# WireLessPhone_Power.net
KiCad netlist of a schematic drawn in Altium Designer
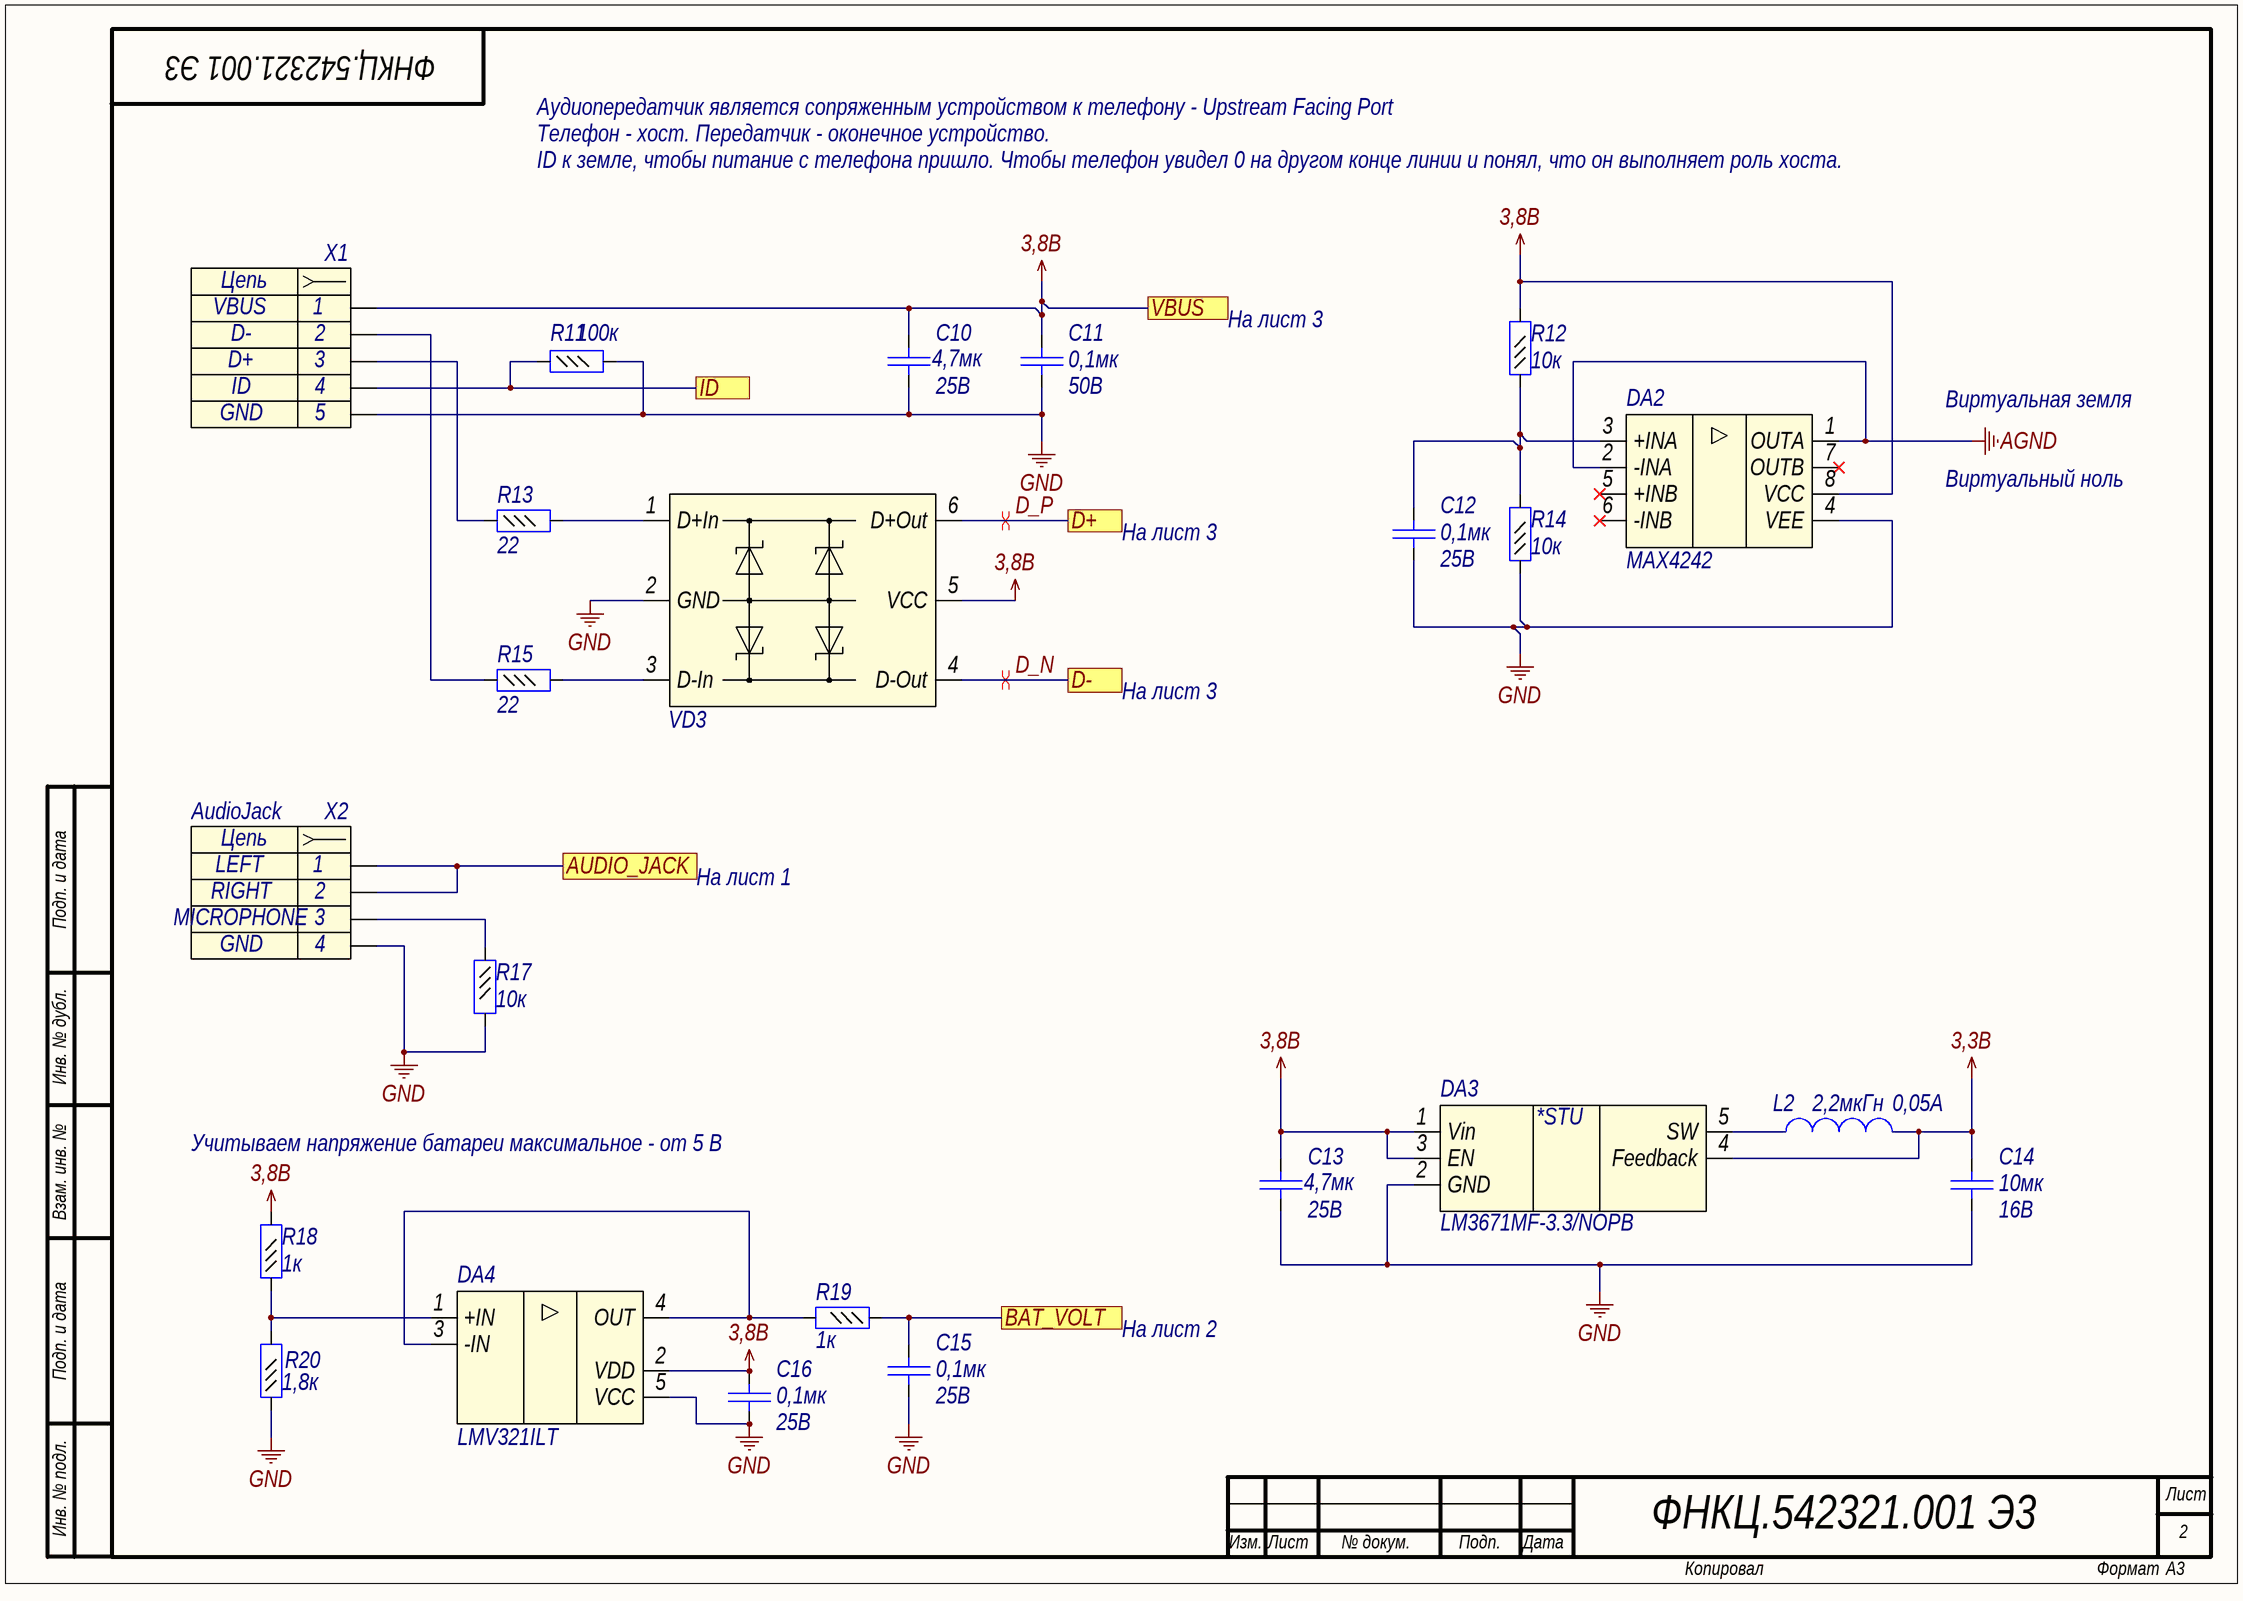
[diagram p0: WireLessPhone_Power.SchDoc]

(export (version "E")
  (design (tool "Eeschema 10.0.6"))
  (components
    (comp (ref "C10")
      (value "4,7мк")
      (footprint "C0805")
      (description "Конденсатор")
      (fields
        (field (name "VOLTAGE") "25B")
        (field (name "PART NUMBER") "GRM21BR61E475KA12L")
        (field (name "Comment") "Capacitor")
      )
      (libsource (lib "MOP44") (part "Capacitor"))
    )
    (comp (ref "C11")
      (value "0,1мк")
      (footprint "C0603")
      (description "Конденсатор")
      (fields
        (field (name "VOLTAGE") "50B")
        (field (name "PART NUMBER") "GRM188R71H104K")
        (field (name "Comment") "Capacitor")
      )
      (libsource (lib "MOP44") (part "Capacitor"))
    )
    (comp (ref "C12")
      (value "0,1мк")
      (footprint "C0402")
      (description "Конденсатор")
      (fields
        (field (name "VOLTAGE") "25B")
        (field (name "PART NUMBER") "GRM155F51E104Z**")
        (field (name "Comment") "Capacitor")
      )
      (libsource (lib "MOP44") (part "Capacitor"))
    )
    (comp (ref "C13")
      (value "4,7мк")
      (footprint "C0805")
      (description "Конденсатор")
      (fields
        (field (name "VOLTAGE") "25B")
        (field (name "PART NUMBER") "GRM21BR61E475KA12L")
        (field (name "Comment") "Capacitor")
      )
      (libsource (lib "MOP44") (part "Capacitor"))
    )
    (comp (ref "C14")
      (value "10мк")
      (footprint "C1206")
      (description "Конденсатор")
      (fields
        (field (name "VOLTAGE") "16В")
        (field (name "PART NUMBER") "GRM31CR71C106K*")
        (field (name "Comment") "Capacitor")
      )
      (libsource (lib "MOP44") (part "Capacitor"))
    )
    (comp (ref "C15")
      (value "0,1мк")
      (footprint "C0402")
      (description "Конденсатор")
      (fields
        (field (name "VOLTAGE") "25B")
        (field (name "PART NUMBER") "GRM155F51E104Z**")
        (field (name "Comment") "Capacitor")
      )
      (libsource (lib "MOP44") (part "Capacitor"))
    )
    (comp (ref "C16")
      (value "0,1мк")
      (footprint "C0402")
      (description "Конденсатор")
      (fields
        (field (name "VOLTAGE") "25B")
        (field (name "PART NUMBER") "GRM155F51E104Z**")
        (field (name "Comment") "Capacitor")
      )
      (libsource (lib "MOP44") (part "Capacitor"))
    )
    (comp (ref "DA2")
      (value "MAX4242")
      (footprint "8µMAX")
      (description "МИКРОМОЩНЫЙ Single/Dual/Quad, +1.8V/10µA, SOT23,  Beyond-the-Rails Op Amps")
      (fields (field (name "PART NUMBER") "MAX4242EUA"))
      (libsource (lib "MOP44") (part "MAX4242"))
    )
    (comp (ref "DA3")
      (value "LM3671MF-3.3/NOPB")
      (footprint "SOT23-5")
      (description "Step-Down DC-DC Converter")
      (fields (field (name "MANUFACTURER") "Texas Instruments"))
      (libsource (lib "MOP44") (part "LM3671MF-3.3/NOPB"))
    )
    (comp (ref "DA4")
      (value "LMV321ILT")
      (footprint "SOT23-5")
      (description "HIGH-DRIVE OPERATIONAL AMPLIFIERS WITH SHUTDOWN")
      (libsource (lib "MOP44") (part "LMV321ILT"))
    )
    (comp (ref "L2")
      (value "2,2мкГн")
      (footprint "L0805")
      (description "EMI Suppression Filter")
      (fields
        (field (name "RATED CURRENT") "0,05A")
        (field (name "PART NUMBER") "MLF2012A2R2KT000")
        (field (name "Comment") "Inductor")
      )
      (libsource (lib "MOP44") (part "Inductor"))
    )
    (comp (ref "R11")
      (value "100к")
      (footprint "R0402")
      (description "Резистор")
      (fields (field (name "PART NUMBER") "RC0402FR-07100KL") (field (name "POWER") "0,062Вт"))
      (libsource (lib "") (part "Resistor_0,062Вт_2"))
    )
    (comp (ref "R12")
      (value "10к")
      (footprint "R0402")
      (description "Резистор")
      (fields (field (name "PART NUMBER") "RC0402FR-0710KL") (field (name "POWER") "0,062Вт"))
      (libsource (lib "") (part "Resistor_0,062Вт_1"))
    )
    (comp (ref "R13")
      (value "22")
      (footprint "R0402")
      (description "Резистор")
      (fields (field (name "PART NUMBER") "RC0402FR-0722RL") (field (name "POWER") "0,062Вт"))
      (libsource (lib "") (part "Resistor_0,062Вт_2"))
    )
    (comp (ref "R14")
      (value "10к")
      (footprint "R0402")
      (description "Резистор")
      (fields (field (name "PART NUMBER") "RC0402FR-0710KL") (field (name "POWER") "0,062Вт"))
      (libsource (lib "") (part "Resistor_0,062Вт_1"))
    )
    (comp (ref "R15")
      (value "22")
      (footprint "R0402")
      (description "Резистор")
      (fields (field (name "PART NUMBER") "RC0402FR-0722RL") (field (name "POWER") "0,062Вт"))
      (libsource (lib "") (part "Resistor_0,062Вт_2"))
    )
    (comp (ref "R17")
      (value "10к")
      (footprint "R0402")
      (description "Резистор")
      (fields (field (name "PART NUMBER") "RC0402FR-0710KL") (field (name "POWER") "0,062Вт"))
      (libsource (lib "") (part "Resistor_0,062Вт_3"))
    )
    (comp (ref "R18")
      (value "1к")
      (footprint "R0402")
      (description "Резистор")
      (fields (field (name "PART NUMBER") "RC0402FR-071KL") (field (name "POWER") "0,062Вт"))
      (libsource (lib "") (part "Resistor_0,062Вт_1"))
    )
    (comp (ref "R19")
      (value "1к")
      (footprint "R0402")
      (description "Резистор")
      (fields (field (name "PART NUMBER") "RC0402FR-071KL") (field (name "POWER") "0,062Вт"))
      (libsource (lib "MOP44") (part "Resistor_0,062Вт"))
    )
    (comp (ref "R20")
      (value "1,8к")
      (footprint "R0402")
      (description "Резистор")
      (fields (field (name "PART NUMBER") "RC0402FR-071K8") (field (name "POWER") "0,062Вт"))
      (libsource (lib "") (part "Resistor_0,062Вт_1"))
    )
    (comp (ref "VD3")
      (value "USBUF")
      (footprint "SOT323-6L")
      (description "EMEMI filter and line termination for USB upstream ports")
      (fields (field (name "PART NUMBER") "USBUF02W6"))
      (libsource (lib "MOP44") (part "USBUF"))
    )
    (comp (ref "X1")
      (value "Header_5_sct")
      (footprint "5HOLE_SMALL")
      (description "Разъем - 5 конт. розетка")
      (libsource (lib "MOP44") (part "Header_5_sct"))
    )
    (comp (ref "X2")
      (value "AudioJack")
      (footprint "4HOLE_SMALL")
      (description "Разъем - 4 конт. розетка")
      (libsource (lib "MOP44") (part "Header_4_sct"))
    )
  )
  (nets
    (net (code "1") (name "/AUDIO_JACK") (class "Default")
      (node (ref "X2") (pin "1") (pinfunction "1_1") (pintype "passive"))
      (node (ref "X2") (pin "2") (pinfunction "2_2") (pintype "passive"))
    )
    (net (code "2") (name "/BAT_VOLT") (class "Default")
      (node (ref "C15") (pin "1") (pinfunction "1_1") (pintype "passive"))
      (node (ref "R19") (pin "1") (pinfunction "1_1") (pintype "passive"))
    )
    (net (code "3") (name "/D_N") (class "Default")
      (node (ref "VD3") (pin "4") (pinfunction "D-Out_4") (pintype "passive"))
    )
    (net (code "4") (name "/D_P") (class "Default")
      (node (ref "VD3") (pin "6") (pinfunction "D+Out_6") (pintype "passive"))
    )
    (net (code "5") (name "/ID") (class "Default")
      (node (ref "R11") (pin "1") (pinfunction "1_1") (pintype "passive"))
      (node (ref "X1") (pin "4") (pinfunction "4_4") (pintype "passive"))
    )
    (net (code "6") (name "3,3B") (class "Default")
      (node (ref "C14") (pin "2") (pinfunction "2_2") (pintype "passive"))
      (node (ref "DA3") (pin "4") (pinfunction "Feedback_4") (pintype "power_in"))
      (node (ref "L2") (pin "2") (pinfunction "2_2") (pintype "passive"))
    )
    (net (code "7") (name "3,8B") (class "Default")
      (node (ref "C10") (pin "2") (pinfunction "2_2") (pintype "passive"))
      (node (ref "C11") (pin "2") (pinfunction "2_2") (pintype "passive"))
      (node (ref "C13") (pin "2") (pinfunction "2_2") (pintype "passive"))
      (node (ref "C16") (pin "1") (pinfunction "1_1") (pintype "passive"))
      (node (ref "DA2") (pin "8") (pinfunction "VCC_8") (pintype "passive"))
      (node (ref "DA3") (pin "1") (pinfunction "Vin_1") (pintype "power_in"))
      (node (ref "DA3") (pin "3") (pinfunction "EN_3") (pintype "power_in"))
      (node (ref "DA4") (pin "2") (pinfunction "VDD_2") (pintype "passive"))
      (node (ref "R12") (pin "2") (pinfunction "2_2") (pintype "passive"))
      (node (ref "R18") (pin "2") (pinfunction "2_2") (pintype "passive"))
      (node (ref "VD3") (pin "5") (pinfunction "VCC_5") (pintype "passive"))
      (node (ref "X1") (pin "1") (pinfunction "1_1") (pintype "passive"))
    )
    (net (code "8") (name "AGND") (class "Default")
      (node (ref "DA2") (pin "1") (pinfunction "OUTA_1") (pintype "passive"))
      (node (ref "DA2") (pin "2") (pinfunction "-INA_2") (pintype "passive"))
    )
    (net (code "9") (name "GND") (class "Default")
      (node (ref "C10") (pin "1") (pinfunction "1_1") (pintype "passive"))
      (node (ref "C11") (pin "1") (pinfunction "1_1") (pintype "passive"))
      (node (ref "C12") (pin "2") (pinfunction "2_2") (pintype "passive"))
      (node (ref "C13") (pin "1") (pinfunction "1_1") (pintype "passive"))
      (node (ref "C14") (pin "1") (pinfunction "1_1") (pintype "passive"))
      (node (ref "C15") (pin "2") (pinfunction "2_2") (pintype "passive"))
      (node (ref "C16") (pin "2") (pinfunction "2_2") (pintype "passive"))
      (node (ref "DA2") (pin "4") (pinfunction "VEE_4") (pintype "passive"))
      (node (ref "DA3") (pin "2") (pinfunction "GND_2") (pintype "power_in"))
      (node (ref "DA4") (pin "5") (pinfunction "VCC_5") (pintype "passive"))
      (node (ref "R11") (pin "2") (pinfunction "2_2") (pintype "passive"))
      (node (ref "R14") (pin "1") (pinfunction "1_1") (pintype "passive"))
      (node (ref "R17") (pin "2") (pinfunction "2_2") (pintype "passive"))
      (node (ref "R20") (pin "1") (pinfunction "1_1") (pintype "passive"))
      (node (ref "VD3") (pin "2") (pinfunction "GND_2") (pintype "passive"))
      (node (ref "X1") (pin "5") (pinfunction "5_5") (pintype "passive"))
      (node (ref "X2") (pin "4") (pinfunction "4_4") (pintype "passive"))
    )
    (net (code "10") (name "Net-(DA2-+INA)") (class "Default")
      (node (ref "C12") (pin "1") (pinfunction "1_1") (pintype "passive"))
      (node (ref "DA2") (pin "3") (pinfunction "+INA_3") (pintype "passive"))
      (node (ref "R12") (pin "1") (pinfunction "1_1") (pintype "passive"))
      (node (ref "R14") (pin "2") (pinfunction "2_2") (pintype "passive"))
    )
    (net (code "11") (name "Net-(DA3-SW)") (class "Default")
      (node (ref "DA3") (pin "5") (pinfunction "SW_5") (pintype "power_in"))
      (node (ref "L2") (pin "1") (pinfunction "1_1") (pintype "passive"))
    )
    (net (code "12") (name "Net-(DA4-+IN)") (class "Default")
      (node (ref "DA4") (pin "1") (pinfunction "+IN_1") (pintype "passive"))
      (node (ref "R18") (pin "1") (pinfunction "1_1") (pintype "passive"))
      (node (ref "R20") (pin "2") (pinfunction "2_2") (pintype "passive"))
    )
    (net (code "13") (name "Net-(DA4--IN)") (class "Default")
      (node (ref "DA4") (pin "3") (pinfunction "-IN_3") (pintype "passive"))
      (node (ref "DA4") (pin "4") (pinfunction "OUT_4") (pintype "passive"))
      (node (ref "R19") (pin "2") (pinfunction "2_2") (pintype "passive"))
    )
    (net (code "14") (name "Net-(R13-Pad1)") (class "Default")
      (node (ref "R13") (pin "1") (pinfunction "1_1") (pintype "passive"))
      (node (ref "X1") (pin "3") (pinfunction "3_3") (pintype "passive"))
    )
    (net (code "15") (name "Net-(R15-Pad1)") (class "Default")
      (node (ref "R15") (pin "1") (pinfunction "1_1") (pintype "passive"))
      (node (ref "X1") (pin "2") (pinfunction "2_2") (pintype "passive"))
    )
    (net (code "16") (name "Net-(R17-Pad1)") (class "Default")
      (node (ref "R17") (pin "1") (pinfunction "1_1") (pintype "passive"))
      (node (ref "X2") (pin "3") (pinfunction "3_3") (pintype "passive"))
    )
    (net (code "17") (name "Net-(VD3-D+In)") (class "Default")
      (node (ref "R13") (pin "2") (pinfunction "2_2") (pintype "passive"))
      (node (ref "VD3") (pin "1") (pinfunction "D+In_1") (pintype "passive"))
    )
    (net (code "18") (name "Net-(VD3-D-In)") (class "Default")
      (node (ref "R15") (pin "2") (pinfunction "2_2") (pintype "passive"))
      (node (ref "VD3") (pin "3") (pinfunction "D-In_3") (pintype "passive"))
    )
    (net (code "19") (name "unconnected-(DA2-+INB-Pad5)") (class "Default")
      (node (ref "DA2") (pin "5") (pinfunction "+INB_5") (pintype "passive+no_connect"))
    )
    (net (code "20") (name "unconnected-(DA2--INB-Pad6)") (class "Default")
      (node (ref "DA2") (pin "6") (pinfunction "-INB_6") (pintype "passive+no_connect"))
    )
    (net (code "21") (name "unconnected-(DA2-OUTB-Pad7)") (class "Default")
      (node (ref "DA2") (pin "7") (pinfunction "OUTB_7") (pintype "passive+no_connect"))
    )
  )
)
